# Sheet1.net
KiCad netlist of a schematic drawn in Altium Designer
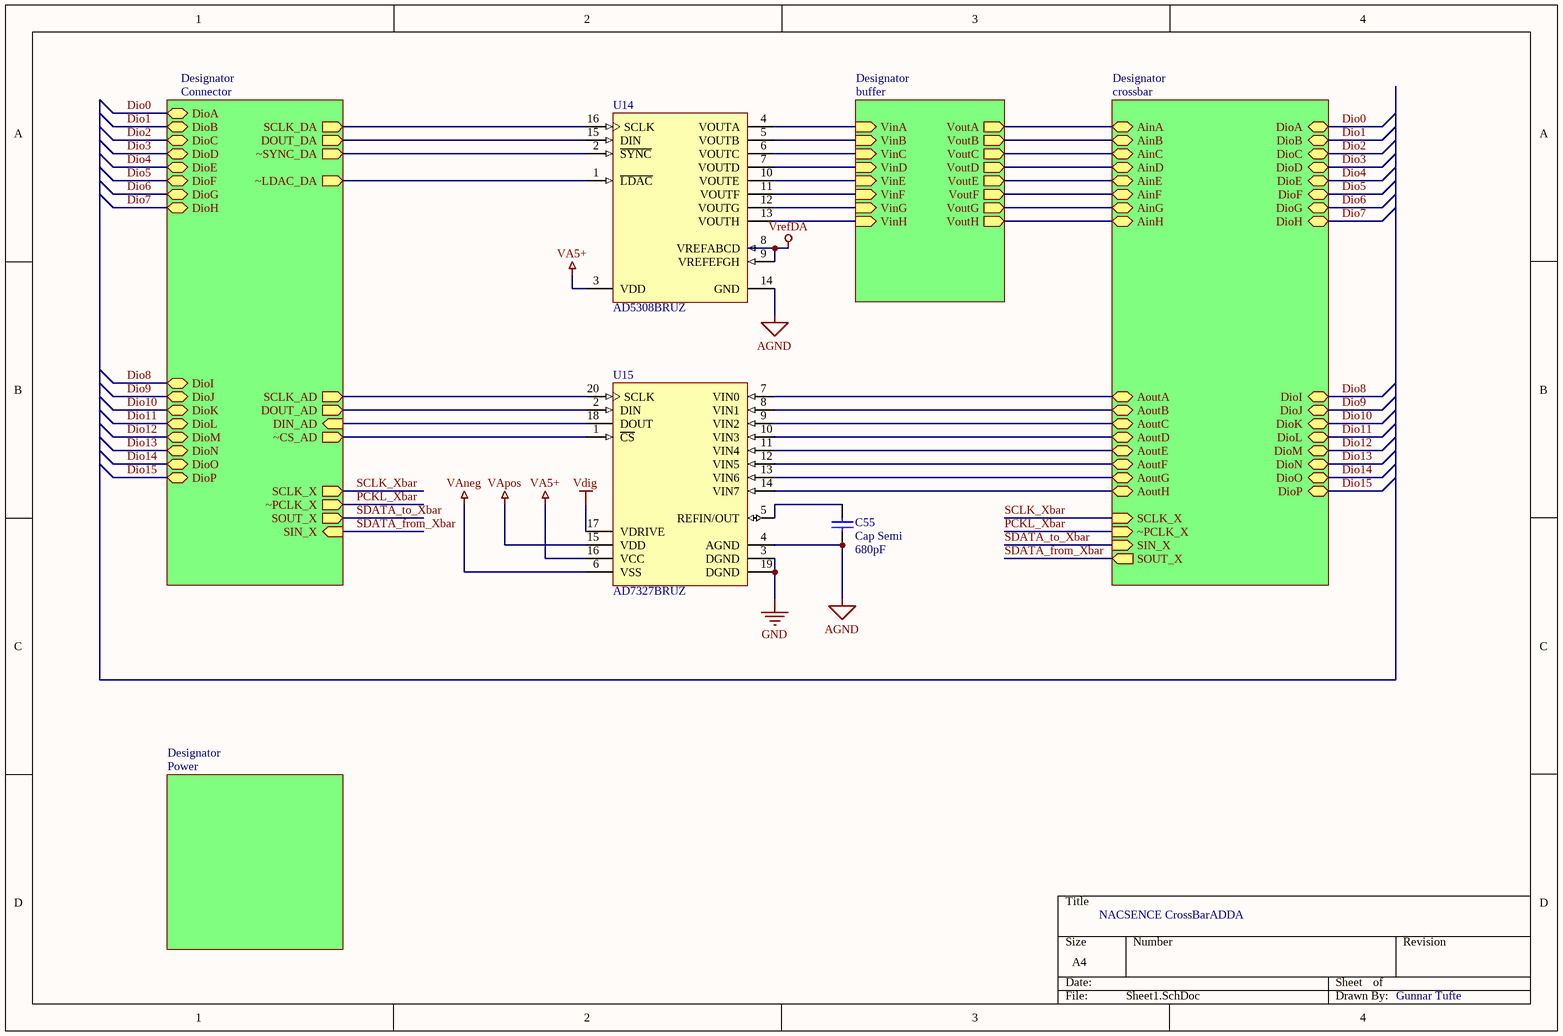
[diagram p0: Sheet1.SchDoc]

(export (version "E")
  (design (tool "Eeschema 10.0.6"))
  (components
    (comp (ref "C55")
      (value "Cap Semi")
      (footprint "C1206")
      (description "Capacitor (Semiconductor SIM Model)")
      (fields (field (name "ALTIUM_VALUE") "680pF") (field (name "PUBLISHER") "Altium Limited"))
      (libsource (lib "Miscellaneous Devices") (part "Cap Semi"))
    )
    (comp (ref "U14")
      (value "AD5308BRUZ")
      (footprint "RU-16_N")
      (fields (field (name "ADI PART NUMBER") "AD5308") (field (name "MANUFACTURER") "Analog Devices"))
      (libsource (lib "Analog Devices Data Converters Digital-to-Analog Converters") (part "AD5308BRUZ"))
    )
    (comp (ref "U15")
      (value "AD7327BRUZ")
      (footprint "RU-20_N")
      (fields (field (name "PART NUMBER") "AD7327") (field (name "MANUFACTURER") "Analog Devices"))
      (libsource (lib "Analog Devices Data Converters Analog-to-Digital Converters") (part "AD7327BRUZ"))
    )
  )
  (nets
    (net (code "1") (name "/AoutA") (class "Default")
      (node (ref "U15") (pin "7") (pinfunction "VIN0_7") (pintype "input"))
    )
    (net (code "2") (name "/AoutB") (class "Default")
      (node (ref "U15") (pin "8") (pinfunction "VIN1_8") (pintype "input"))
    )
    (net (code "3") (name "/AoutC") (class "Default")
      (node (ref "U15") (pin "9") (pinfunction "VIN2_9") (pintype "input"))
    )
    (net (code "4") (name "/AoutD") (class "Default")
      (node (ref "U15") (pin "10") (pinfunction "VIN3_10") (pintype "input"))
    )
    (net (code "5") (name "/AoutE") (class "Default")
      (node (ref "U15") (pin "11") (pinfunction "VIN4_11") (pintype "input"))
    )
    (net (code "6") (name "/AoutF") (class "Default")
      (node (ref "U15") (pin "12") (pinfunction "VIN5_12") (pintype "input"))
    )
    (net (code "7") (name "/AoutG") (class "Default")
      (node (ref "U15") (pin "13") (pinfunction "VIN6_13") (pintype "input"))
    )
    (net (code "8") (name "/AoutH") (class "Default")
      (node (ref "U15") (pin "14") (pinfunction "VIN7_14") (pintype "input"))
    )
    (net (code "9") (name "/DIN_AD") (class "Default")
      (node (ref "U15") (pin "18") (pinfunction "DOUT_18") (pintype "tri_state"))
    )
    (net (code "10") (name "/DOUT_AD") (class "Default")
      (node (ref "U15") (pin "2") (pinfunction "DIN_2") (pintype "input"))
    )
    (net (code "11") (name "/DOUT_DA") (class "Default")
      (node (ref "U14") (pin "15") (pinfunction "DIN_15") (pintype "input"))
    )
    (net (code "29") (name "/SCLK_AD") (class "Default")
      (node (ref "U15") (pin "20") (pinfunction "SCLK_20") (pintype "input"))
    )
    (net (code "30") (name "/SCLK_DA") (class "Default")
      (node (ref "U14") (pin "16") (pinfunction "SCLK_16") (pintype "input"))
    )
    (net (code "34") (name "/VinA") (class "Default")
      (node (ref "U14") (pin "4") (pinfunction "VOUTA_4") (pintype "tri_state"))
    )
    (net (code "35") (name "/VinB") (class "Default")
      (node (ref "U14") (pin "5") (pinfunction "VOUTB_5") (pintype "tri_state"))
    )
    (net (code "36") (name "/VinC") (class "Default")
      (node (ref "U14") (pin "6") (pinfunction "VOUTC_6") (pintype "tri_state"))
    )
    (net (code "37") (name "/VinD") (class "Default")
      (node (ref "U14") (pin "7") (pinfunction "VOUTD_7") (pintype "tri_state"))
    )
    (net (code "38") (name "/VinE") (class "Default")
      (node (ref "U14") (pin "10") (pinfunction "VOUTE_10") (pintype "tri_state"))
    )
    (net (code "39") (name "/VinF") (class "Default")
      (node (ref "U14") (pin "11") (pinfunction "VOUTF_11") (pintype "tri_state"))
    )
    (net (code "40") (name "/VinG") (class "Default")
      (node (ref "U14") (pin "12") (pinfunction "VOUTG_12") (pintype "tri_state"))
    )
    (net (code "41") (name "/VinH") (class "Default")
      (node (ref "U14") (pin "13") (pinfunction "VOUTH_13") (pintype "tri_state"))
    )
    (net (code "50") (name "/~CS_AD") (class "Default")
      (node (ref "U15") (pin "1") (pinfunction "~{CS}_1") (pintype "input"))
    )
    (net (code "51") (name "/~LDAC_DA") (class "Default")
      (node (ref "U14") (pin "1") (pinfunction "~{LDAC}_1") (pintype "input"))
    )
    (net (code "52") (name "/~SYNC_DA") (class "Default")
      (node (ref "U14") (pin "2") (pinfunction "~{SYNC}_2") (pintype "input"))
    )
    (net (code "53") (name "AGND") (class "Default")
      (node (ref "C55") (pin "2") (pinfunction "2_2") (pintype "passive"))
      (node (ref "U14") (pin "14") (pinfunction "GND_14") (pintype "power_in"))
      (node (ref "U15") (pin "4") (pinfunction "AGND_4") (pintype "power_in"))
    )
    (net (code "54") (name "GND") (class "Default")
      (node (ref "U15") (pin "19") (pinfunction "DGND_19") (pintype "power_in"))
      (node (ref "U15") (pin "3") (pinfunction "DGND_3") (pintype "power_in"))
    )
    (net (code "55") (name "Net-(U15-REFIN{slash}OUT)") (class "Default")
      (node (ref "C55") (pin "1") (pinfunction "1_1") (pintype "passive"))
      (node (ref "U15") (pin "5") (pinfunction "REFIN/OUT_5") (pintype "bidirectional"))
    )
    (net (code "56") (name "VA5+") (class "Default")
      (node (ref "U14") (pin "3") (pinfunction "VDD_3") (pintype "power_in"))
      (node (ref "U15") (pin "16") (pinfunction "VCC_16") (pintype "power_in"))
    )
    (net (code "57") (name "VAneg") (class "Default")
      (node (ref "U15") (pin "6") (pinfunction "VSS_6") (pintype "power_in"))
    )
    (net (code "58") (name "VApos") (class "Default")
      (node (ref "U15") (pin "15") (pinfunction "VDD_15") (pintype "power_in"))
    )
    (net (code "59") (name "Vdig") (class "Default")
      (node (ref "U15") (pin "17") (pinfunction "VDRIVE_17") (pintype "power_in"))
    )
    (net (code "60") (name "VrefDA") (class "Default")
      (node (ref "U14") (pin "8") (pinfunction "VREFABCD_8") (pintype "input"))
      (node (ref "U14") (pin "9") (pinfunction "VREFEFGH_9") (pintype "input"))
    )
  )
)
